# Printrhub_Rev_0_2.net
KiCad netlist of a schematic drawn in EAGLE
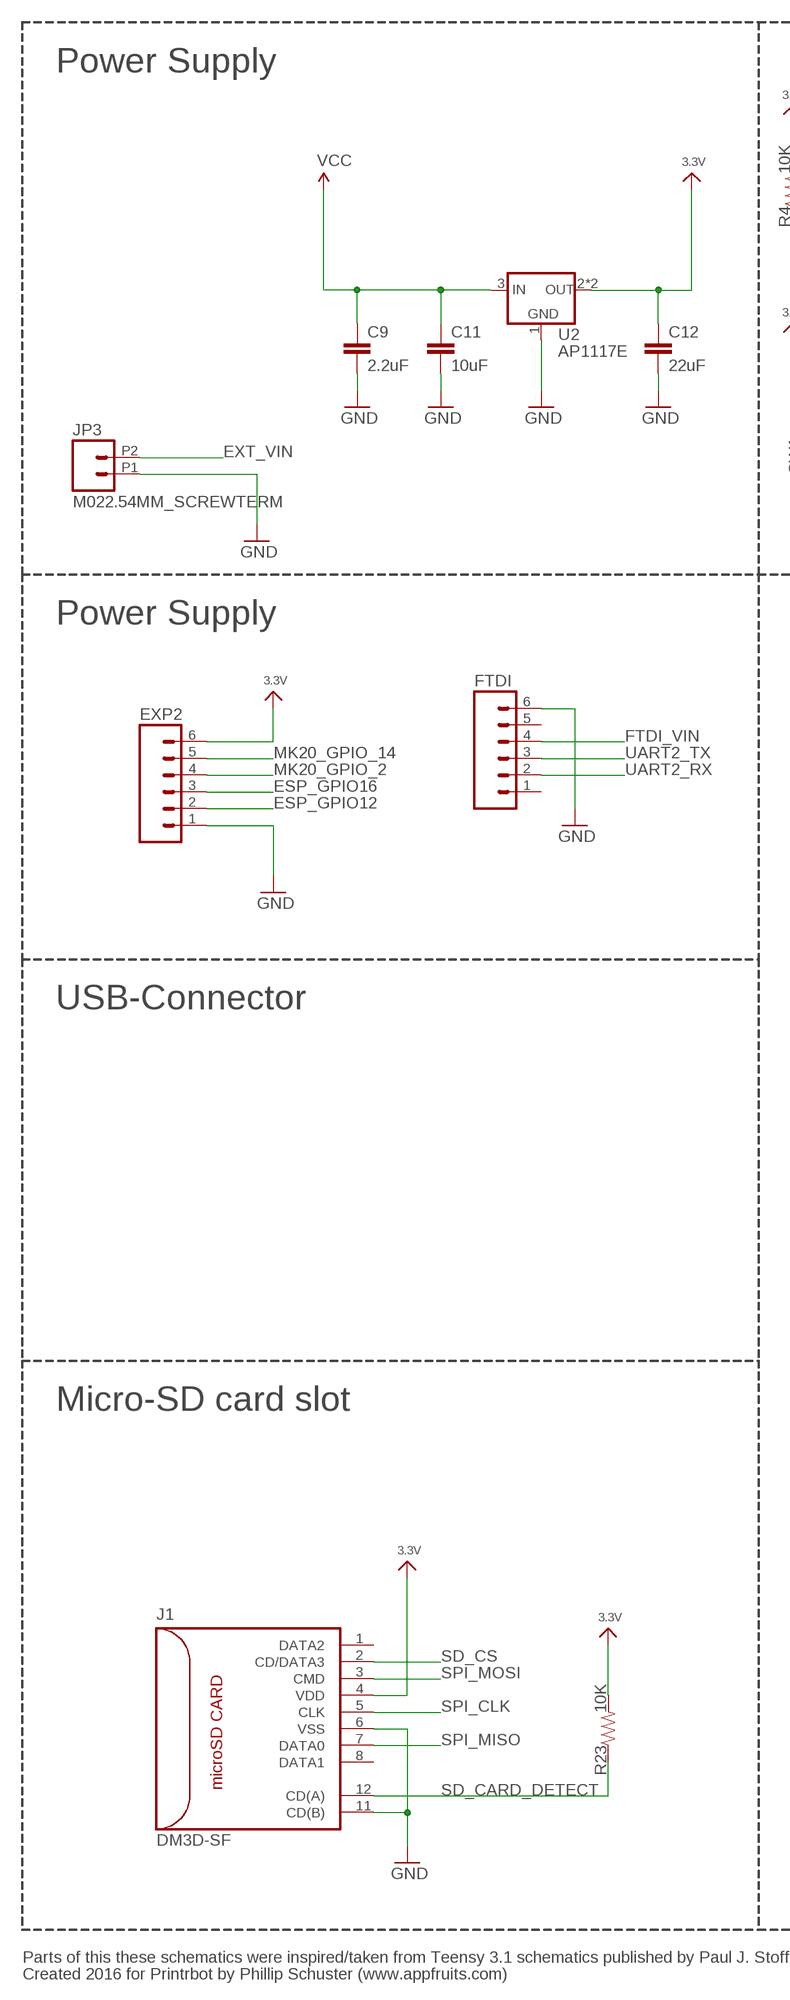
[diagram p0: schematic, sheet 1, part 1 of 2]
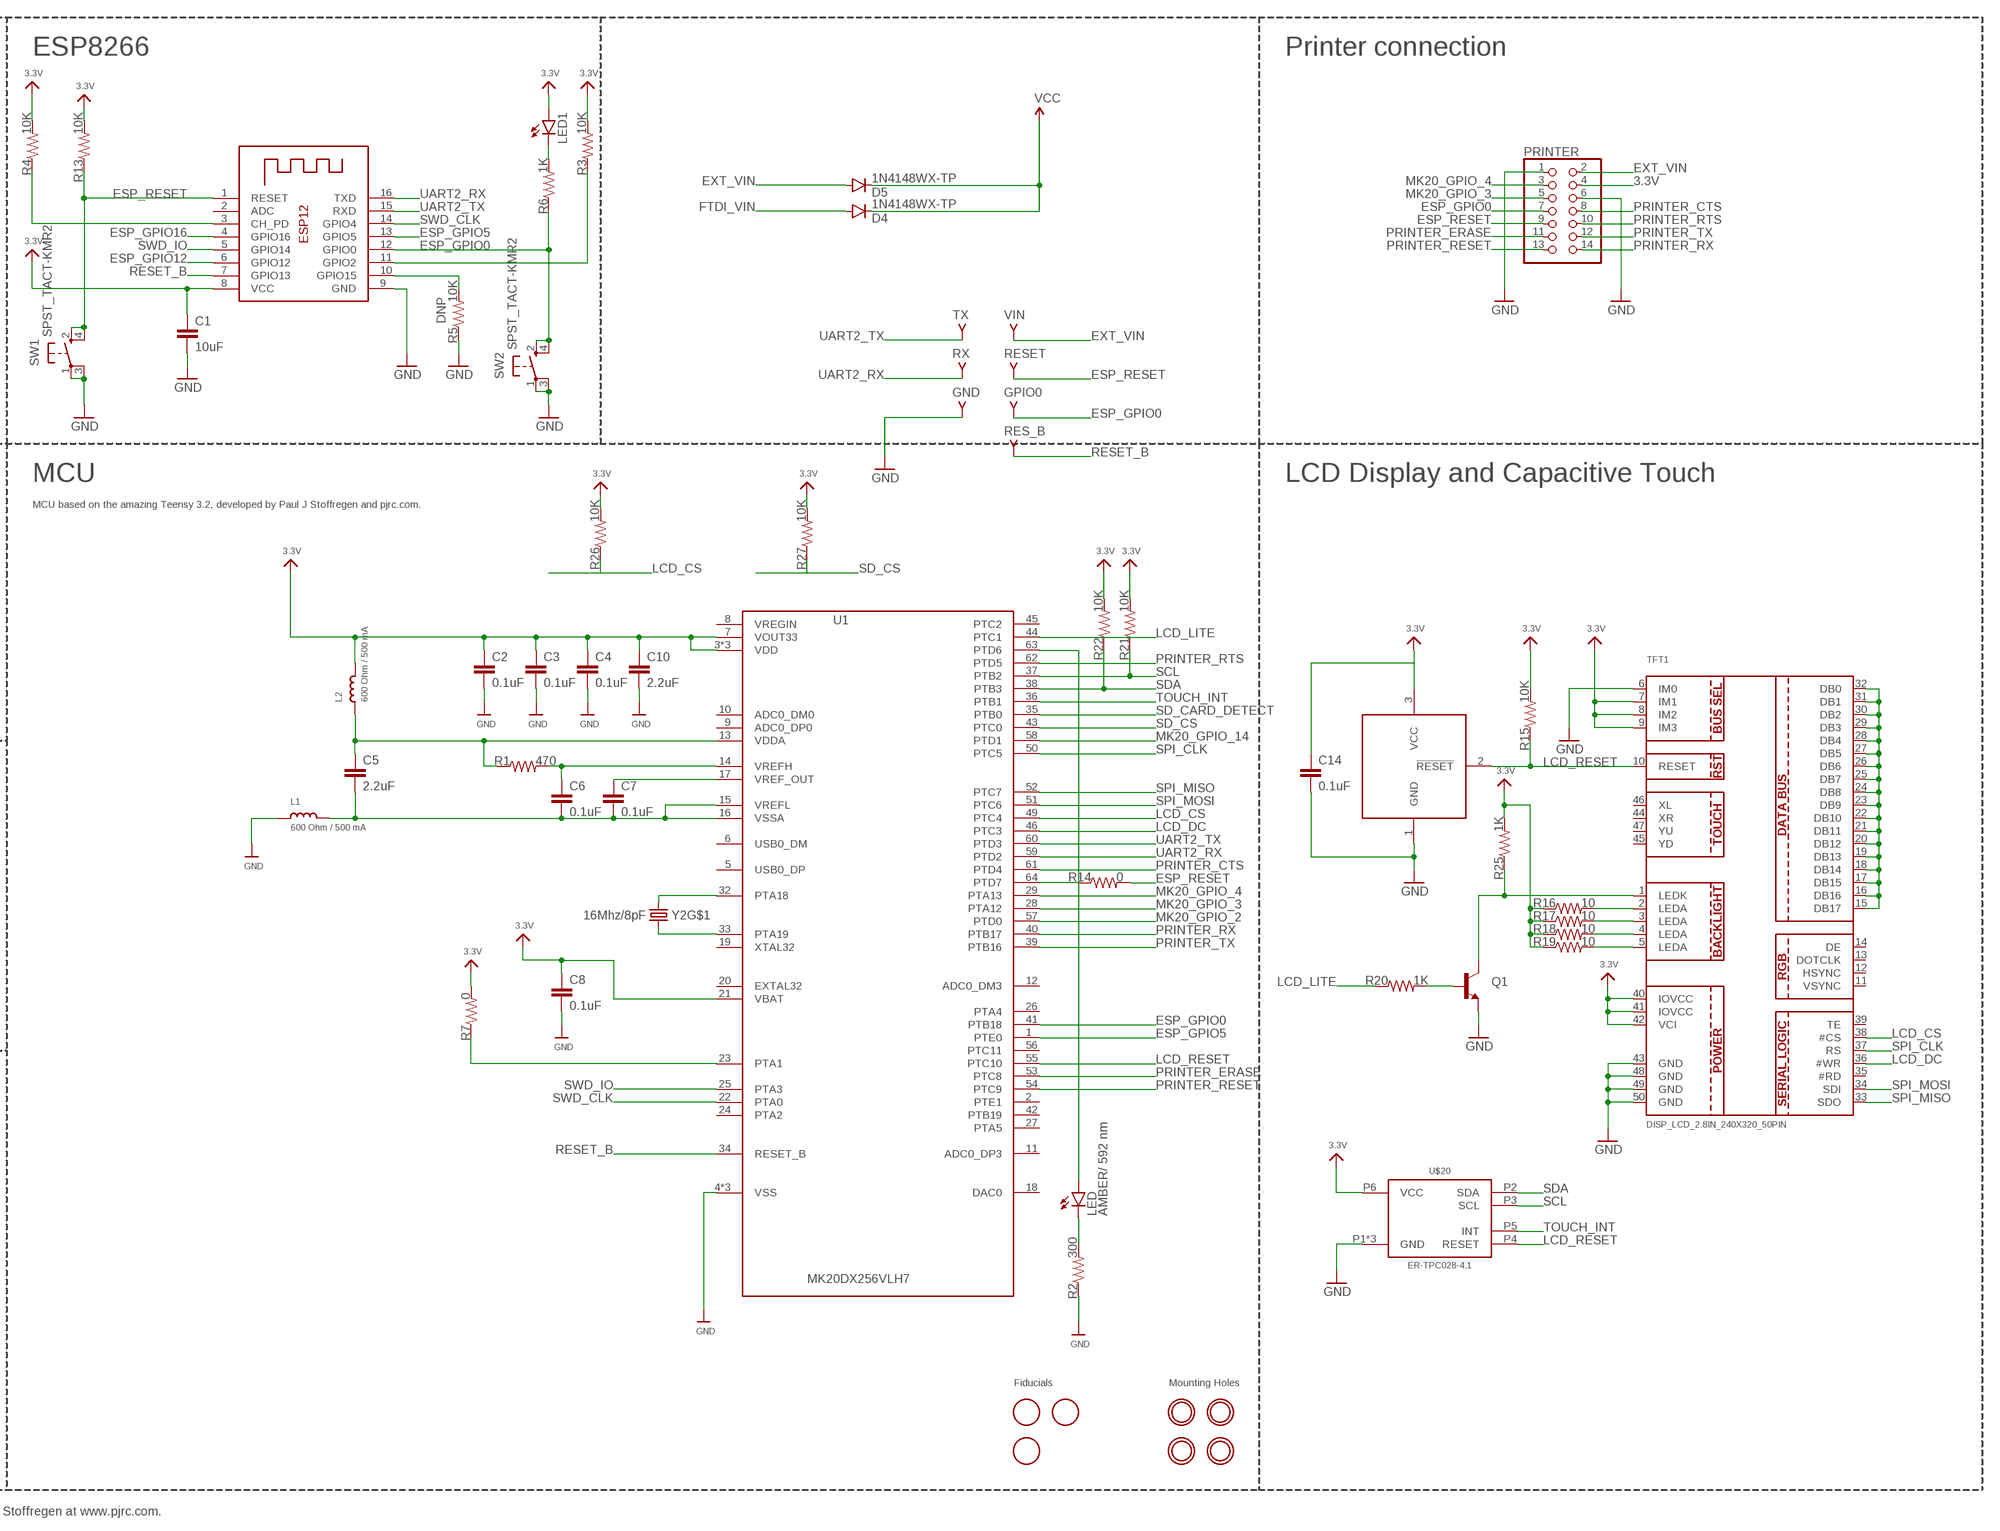
[diagram p1: schematic, sheet 1, part 2 of 2]

(export (version "E")
  (design (tool "Eeschema 10.0.6"))
  (components
    (comp (ref "C1")
      (value "10uF")
      (footprint "eagle-import:0603-CAP")
      (fields (field (name "MF") "Murata") (field (name "MPN") "GRM188R60J106ME47D"))
      (libsource (lib "eagle-import") (part "CAPACITOR-10UF"))
    )
    (comp (ref "C2")
      (value "0.1uF")
      (footprint "eagle-import:0603-CAP")
      (fields (field (name "MF") "Kemet") (field (name "MPN") "C0603C104J3RACTU"))
      (libsource (lib "eagle-import") (part "CAPACITOR-0.1UF"))
    )
    (comp (ref "C3")
      (value "0.1uF")
      (footprint "eagle-import:0603-CAP")
      (fields (field (name "MF") "Kemet") (field (name "MPN") "C0603C104J3RACTU"))
      (libsource (lib "eagle-import") (part "CAPACITOR-0.1UF"))
    )
    (comp (ref "C4")
      (value "0.1uF")
      (footprint "eagle-import:0603-CAP")
      (fields (field (name "MF") "Kemet") (field (name "MPN") "C0603C104J3RACTU"))
      (libsource (lib "eagle-import") (part "CAPACITOR-0.1UF"))
    )
    (comp (ref "C5")
      (value "2.2uF")
      (footprint "eagle-import:0603-CAP")
      (fields (field (name "MF") "Kemet") (field (name "MPN") "C0603C225K4PACTU"))
      (libsource (lib "eagle-import") (part "CAPACITOR-2.2UF"))
    )
    (comp (ref "C6")
      (value "0.1uF")
      (footprint "eagle-import:0603-CAP")
      (fields (field (name "MF") "Kemet") (field (name "MPN") "C0603C104J3RACTU"))
      (libsource (lib "eagle-import") (part "CAPACITOR-0.1UF"))
    )
    (comp (ref "C7")
      (value "0.1uF")
      (footprint "eagle-import:0603-CAP")
      (fields (field (name "MF") "Kemet") (field (name "MPN") "C0603C104J3RACTU"))
      (libsource (lib "eagle-import") (part "CAPACITOR-0.1UF"))
    )
    (comp (ref "C8")
      (value "0.1uF")
      (footprint "eagle-import:0603-CAP")
      (fields (field (name "MF") "Kemet") (field (name "MPN") "C0603C104J3RACTU"))
      (libsource (lib "eagle-import") (part "CAPACITOR-0.1UF"))
    )
    (comp (ref "C9")
      (value "2.2uF")
      (footprint "eagle-import:0603-CAP")
      (fields (field (name "MF") "Kemet") (field (name "MPN") "C0603C225K4PACTU"))
      (libsource (lib "eagle-import") (part "CAPACITOR-2.2UF"))
    )
    (comp (ref "C10")
      (value "2.2uF")
      (footprint "eagle-import:0603-CAP")
      (fields (field (name "MF") "Kemet") (field (name "MPN") "C0603C225K4PACTU"))
      (libsource (lib "eagle-import") (part "CAPACITOR-2.2UF"))
    )
    (comp (ref "C11")
      (value "10uF")
      (footprint "eagle-import:0603-CAP")
      (fields (field (name "MF") "Murata") (field (name "MPN") "GRM188R60J106ME47D"))
      (libsource (lib "eagle-import") (part "CAPACITOR-10UF"))
    )
    (comp (ref "C12")
      (value "22uF")
      (footprint "eagle-import:0603-CAP")
      (fields (field (name "MF") "Murata") (field (name "MPN") "GRM188R60J226MEA0D"))
      (libsource (lib "eagle-import") (part "CAPACITOR-22UF"))
    )
    (comp (ref "C14")
      (value "0.1uF")
      (footprint "eagle-import:0603-CAP")
      (fields (field (name "MF") "Kemet") (field (name "MPN") "C0603C104J3RACTU"))
      (libsource (lib "eagle-import") (part "CAPACITOR-0.1UF"))
    )
    (comp (ref "D4")
      (value "1N4148WX-TP")
      (footprint "eagle-import:SOD-323")
      (fields (field (name "MF") "Micro Commercial Co"))
      (libsource (lib "eagle-import") (part "DIODESOD"))
    )
    (comp (ref "D5")
      (value "1N4148WX-TP")
      (footprint "eagle-import:SOD-323")
      (fields (field (name "MF") "Micro Commercial Co"))
      (libsource (lib "eagle-import") (part "DIODESOD"))
    )
    (comp (ref "EXP2")
      (value "M06SMD-STRAIGHT-ALT")
      (footprint "eagle-import:1X06_SMD_STRAIGHT_ALT")
      (libsource (lib "eagle-import") (part "M06SMD-STRAIGHT-ALT"))
    )
    (comp (ref "FTDI")
      (value "M06SMD-STRAIGHT-ALT")
      (footprint "eagle-import:1X06_SMD_STRAIGHT_ALT")
      (libsource (lib "eagle-import") (part "M06SMD-STRAIGHT-ALT"))
    )
    (comp (ref "GND")
      (value "TPV-SMD-18RN")
      (footprint "eagle-import:SMD-18RN")
      (libsource (lib "eagle-import") (part "TPV-SMD-18RN"))
    )
    (comp (ref "GPIO0")
      (value "TPV-SMD-18RN")
      (footprint "eagle-import:SMD-18RN")
      (libsource (lib "eagle-import") (part "TPV-SMD-18RN"))
    )
    (comp (ref "J1")
      (value "DM3D-SF")
      (footprint "eagle-import:DM3D-SF")
      (libsource (lib "eagle-import") (part "DM3D-SF"))
    )
    (comp (ref "JP3")
      (value "M022.54MM_SCREWTERM")
      (footprint "eagle-import:1X02_2.54_SCREWTERM")
      (libsource (lib "eagle-import") (part "M022.54MM_SCREWTERM"))
    )
    (comp (ref "L1")
      (value "600 Ohm / 500 mA")
      (footprint "eagle-import:0603")
      (fields (field (name "MF") "Murata") (field (name "MPN") "BLM18AG601SN1D"))
      (libsource (lib "eagle-import") (part "INDUCTOR-0603_600OHM/500MA"))
    )
    (comp (ref "L2")
      (value "600 Ohm / 500 mA")
      (footprint "eagle-import:0603")
      (fields (field (name "MF") "Murata") (field (name "MPN") "BLM18AG601SN1D"))
      (libsource (lib "eagle-import") (part "INDUCTOR-0603_600OHM/500MA"))
    )
    (comp (ref "LED")
      (value "AMBER/ 592 nm")
      (footprint "eagle-import:LED-0603")
      (fields (field (name "MF") "Avago Technologies") (field (name "MPN") "HSMA-C190"))
      (libsource (lib "eagle-import") (part "LED-AMBER"))
    )
    (comp (ref "LED1")
      (value "LED-GREEN")
      (footprint "eagle-import:LED-0603")
      (fields (field (name "MF") "Avago") (field (name "MPN") "HSMG-C190"))
      (libsource (lib "eagle-import") (part "LED-GREEN"))
    )
    (comp (ref "PRINTER")
      (value "PINHD-2X7SMT")
      (footprint "eagle-import:2X07_SMT")
      (libsource (lib "eagle-import") (part "PINHD-2X7SMT"))
    )
    (comp (ref "Q1")
      (value "TRANSISTOR_NPNSOT23-3")
      (footprint "eagle-import:SOT23-3")
      (fields (field (name "MF") "ON Semiconductor") (field (name "MPN") "MMBT2222ALT1G"))
      (libsource (lib "eagle-import") (part "TRANSISTOR_NPNSOT23-3"))
    )
    (comp (ref "R1")
      (value "470")
      (footprint "eagle-import:0603-RES")
      (fields (field (name "MF") "Panasonic") (field (name "MPN") "ERJ-3GEYJ471V"))
      (libsource (lib "eagle-import") (part "RESISTOR-470"))
    )
    (comp (ref "R2")
      (value "300")
      (footprint "eagle-import:0603-RES")
      (libsource (lib "eagle-import") (part "RESISTOR0603"))
    )
    (comp (ref "R3")
      (value "10K")
      (footprint "eagle-import:0603-RES")
      (fields (field (name "MF") "Panasonic") (field (name "MPN") "ERJ-3GEYJ103V"))
      (libsource (lib "eagle-import") (part "RESISTOR-10K"))
    )
    (comp (ref "R4")
      (value "10K")
      (footprint "eagle-import:0603-RES")
      (fields (field (name "MF") "Panasonic") (field (name "MPN") "ERJ-3GEYJ103V"))
      (libsource (lib "eagle-import") (part "RESISTOR-10K"))
    )
    (comp (ref "R5")
      (value "10K")
      (footprint "eagle-import:0603-RES")
      (fields (field (name "MF") "Panasonic") (field (name "MPN") "ERJ-3GEYJ103V"))
      (libsource (lib "eagle-import") (part "RESISTOR-10K"))
    )
    (comp (ref "R6")
      (value "1K")
      (footprint "eagle-import:0603-RES")
      (fields (field (name "MF") "Panasonic") (field (name "MPN") "ERJ-3GEYJ102V"))
      (libsource (lib "eagle-import") (part "RESISTOR-1K"))
    )
    (comp (ref "R7")
      (value "0")
      (footprint "eagle-import:0603-RES")
      (fields (field (name "MF") "Panasonic") (field (name "MPN") "ERJ-3GEY0R00V"))
      (libsource (lib "eagle-import") (part "RESISTOR-0"))
    )
    (comp (ref "R13")
      (value "10K")
      (footprint "eagle-import:0603-RES")
      (fields (field (name "MF") "Panasonic") (field (name "MPN") "ERJ-3GEYJ103V"))
      (libsource (lib "eagle-import") (part "RESISTOR-10K"))
    )
    (comp (ref "R14")
      (value "0")
      (footprint "eagle-import:0603-RES")
      (fields (field (name "MF") "Panasonic") (field (name "MPN") "ERJ-3GEY0R00V"))
      (libsource (lib "eagle-import") (part "RESISTOR-0"))
    )
    (comp (ref "R15")
      (value "10K")
      (footprint "eagle-import:0603-RES")
      (fields (field (name "MF") "Panasonic") (field (name "MPN") "ERJ-3GEYJ103V"))
      (libsource (lib "eagle-import") (part "RESISTOR-10K"))
    )
    (comp (ref "R16")
      (value "10")
      (footprint "eagle-import:0603-RES")
      (fields (field (name "MF") "Panasonic") (field (name "MPN") "ERJ-3EKF10R0V"))
      (libsource (lib "eagle-import") (part "RESISTOR-10"))
    )
    (comp (ref "R17")
      (value "10")
      (footprint "eagle-import:0603-RES")
      (fields (field (name "MF") "Panasonic") (field (name "MPN") "ERJ-3EKF10R0V"))
      (libsource (lib "eagle-import") (part "RESISTOR-10"))
    )
    (comp (ref "R18")
      (value "10")
      (footprint "eagle-import:0603-RES")
      (fields (field (name "MF") "Panasonic") (field (name "MPN") "ERJ-3EKF10R0V"))
      (libsource (lib "eagle-import") (part "RESISTOR-10"))
    )
    (comp (ref "R19")
      (value "10")
      (footprint "eagle-import:0603-RES")
      (fields (field (name "MF") "Panasonic") (field (name "MPN") "ERJ-3EKF10R0V"))
      (libsource (lib "eagle-import") (part "RESISTOR-10"))
    )
    (comp (ref "R20")
      (value "1K")
      (footprint "eagle-import:0603-RES")
      (fields (field (name "MF") "Panasonic") (field (name "MPN") "ERJ-3GEYJ102V"))
      (libsource (lib "eagle-import") (part "RESISTOR-1K"))
    )
    (comp (ref "R21")
      (value "10K")
      (footprint "eagle-import:0603-RES")
      (fields (field (name "MF") "Panasonic") (field (name "MPN") "ERJ-3GEYJ103V"))
      (libsource (lib "eagle-import") (part "RESISTOR-10K"))
    )
    (comp (ref "R22")
      (value "10K")
      (footprint "eagle-import:0603-RES")
      (fields (field (name "MF") "Panasonic") (field (name "MPN") "ERJ-3GEYJ103V"))
      (libsource (lib "eagle-import") (part "RESISTOR-10K"))
    )
    (comp (ref "R23")
      (value "10K")
      (footprint "eagle-import:0603-RES")
      (fields (field (name "MF") "Panasonic") (field (name "MPN") "ERJ-3GEYJ103V"))
      (libsource (lib "eagle-import") (part "RESISTOR-10K"))
    )
    (comp (ref "R25")
      (value "1K")
      (footprint "eagle-import:0603-RES")
      (fields (field (name "MF") "Panasonic") (field (name "MPN") "ERJ-3GEYJ102V"))
      (libsource (lib "eagle-import") (part "RESISTOR-1K"))
    )
    (comp (ref "R26")
      (value "10K")
      (footprint "eagle-import:0603-RES")
      (fields (field (name "MF") "Panasonic") (field (name "MPN") "ERJ-3GEYJ103V"))
      (libsource (lib "eagle-import") (part "RESISTOR-10K"))
    )
    (comp (ref "R27")
      (value "10K")
      (footprint "eagle-import:0603-RES")
      (fields (field (name "MF") "Panasonic") (field (name "MPN") "ERJ-3GEYJ103V"))
      (libsource (lib "eagle-import") (part "RESISTOR-10K"))
    )
    (comp (ref "RESET")
      (value "TPV-SMD-18RN")
      (footprint "eagle-import:SMD-18RN")
      (libsource (lib "eagle-import") (part "TPV-SMD-18RN"))
    )
    (comp (ref "RES_B")
      (value "TPV-SMD-18RN")
      (footprint "eagle-import:SMD-18RN")
      (libsource (lib "eagle-import") (part "TPV-SMD-18RN"))
    )
    (comp (ref "RX")
      (value "TPV-SMD-18RN")
      (footprint "eagle-import:SMD-18RN")
      (libsource (lib "eagle-import") (part "TPV-SMD-18RN"))
    )
    (comp (ref "SW1")
      (value "SPST_TACT-KMR2")
      (footprint "eagle-import:KMR2")
      (libsource (lib "eagle-import") (part "SPST_TACT-KMR2"))
    )
    (comp (ref "SW2")
      (value "SPST_TACT-KMR2")
      (footprint "eagle-import:KMR2")
      (libsource (lib "eagle-import") (part "SPST_TACT-KMR2"))
    )
    (comp (ref "TFT1")
      (value "DISP_LCD_2.8IN_240X320_50PIN")
      (footprint "eagle-import:TFT_2.83IN_240X320_50PIN")
      (libsource (lib "eagle-import") (part "DISP_LCD_2.8IN_240X320_50PIN"))
    )
    (comp (ref "TX")
      (value "TPV-SMD-18RN")
      (footprint "eagle-import:SMD-18RN")
      (libsource (lib "eagle-import") (part "TPV-SMD-18RN"))
    )
    (comp (ref "U$15")
      (value "MOUNTINGHOLE2.0")
      (footprint "eagle-import:MOUNTINGHOLE_2.0_PLATED")
      (libsource (lib "eagle-import") (part "MOUNTINGHOLE2.0"))
    )
    (comp (ref "U$16")
      (value "MOUNTINGHOLE2.0")
      (footprint "eagle-import:MOUNTINGHOLE_2.0_PLATED")
      (libsource (lib "eagle-import") (part "MOUNTINGHOLE2.0"))
    )
    (comp (ref "U$17")
      (value "MOUNTINGHOLE2.0")
      (footprint "eagle-import:MOUNTINGHOLE_2.0_PLATED")
      (libsource (lib "eagle-import") (part "MOUNTINGHOLE2.0"))
    )
    (comp (ref "U$18")
      (value "MOUNTINGHOLE2.0")
      (footprint "eagle-import:MOUNTINGHOLE_2.0_PLATED")
      (libsource (lib "eagle-import") (part "MOUNTINGHOLE2.0"))
    )
    (comp (ref "U$20")
      (value "ER-TPC028-4.1")
      (footprint "eagle-import:ER-CON06HB-1")
      (libsource (lib "eagle-import") (part "ER-TPC028-4.1"))
    )
    (comp (ref "U$38")
      (value "FIDUCIAL")
      (footprint "eagle-import:FIDUCIAL_1MM")
      (libsource (lib "eagle-import") (part "FIDUCIAL"))
    )
    (comp (ref "U$39")
      (value "FIDUCIAL")
      (footprint "eagle-import:FIDUCIAL_1MM")
      (libsource (lib "eagle-import") (part "FIDUCIAL"))
    )
    (comp (ref "U$40")
      (value "FIDUCIAL")
      (footprint "eagle-import:FIDUCIAL_1MM")
      (libsource (lib "eagle-import") (part "FIDUCIAL"))
    )
    (comp (ref "U1")
      (value "MK20DX256VLH7")
      (footprint "eagle-import:MK20DX256VLH7")
      (fields (field (name "MF") "Freescale"))
      (libsource (lib "eagle-import") (part "MK20DX256VLH7"))
    )
    (comp (ref "U2")
      (value "AP1117E")
      (footprint "eagle-import:SOT223")
      (libsource (lib "eagle-import") (part "AP1117E"))
    )
    (comp (ref "U3")
      (value "MAX308-SOT23")
      (footprint "eagle-import:SOT23")
      (libsource (lib "eagle-import") (part "MAX308-SOT23"))
    )
    (comp (ref "VIN")
      (value "TPV-SMD-18RN")
      (footprint "eagle-import:SMD-18RN")
      (libsource (lib "eagle-import") (part "TPV-SMD-18RN"))
    )
    (comp (ref "X1")
      (value "ESP-12")
      (footprint "eagle-import:ESP-12")
      (libsource (lib "eagle-import") (part "ESP-12"))
    )
    (comp (ref "Y2")
      (value "16Mhz/8pF")
      (footprint "eagle-import:CRYSTAL-SMD-5X3")
      (fields (field (name "MF") "ECS") (field (name "MPN") "ECS-160-8-30B-CKM"))
      (libsource (lib "eagle-import") (part "CRYSTAL/SMD-5X3-GND16MHZ/8PF"))
    )
  )
  (nets
    (net (code "1") (name "/ESP_GPIO0") (class "Default")
      (node (ref "GPIO0") (pin "TP") (pinfunction "TP_TP") (pintype "passive"))
      (node (ref "PRINTER") (pin "7") (pinfunction "7_7") (pintype "passive"))
      (node (ref "R6") (pin "1") (pinfunction "1_1") (pintype "passive"))
      (node (ref "SW2") (pin "2") (pinfunction "S_2") (pintype "passive"))
      (node (ref "SW2") (pin "4") (pinfunction "S1_4") (pintype "passive"))
      (node (ref "U1") (pin "41") (pinfunction "PTB18_41") (pintype "bidirectional"))
      (node (ref "X1") (pin "12") (pinfunction "GPIO0_12") (pintype "bidirectional"))
    )
    (net (code "2") (name "/ESP_GPIO5") (class "Default")
      (node (ref "U1") (pin "1") (pinfunction "PTE0_1") (pintype "bidirectional"))
      (node (ref "X1") (pin "13") (pinfunction "GPIO5_13") (pintype "bidirectional"))
    )
    (net (code "3") (name "/ESP_GPIO12") (class "Default")
      (node (ref "EXP2") (pin "2") (pinfunction "2_2") (pintype "passive"))
      (node (ref "X1") (pin "6") (pinfunction "GPIO12_6") (pintype "bidirectional"))
    )
    (net (code "4") (name "/ESP_GPIO16") (class "Default")
      (node (ref "EXP2") (pin "3") (pinfunction "3_3") (pintype "passive"))
      (node (ref "X1") (pin "4") (pinfunction "GPIO16_4") (pintype "bidirectional"))
    )
    (net (code "5") (name "/ESP_RESET") (class "Default")
      (node (ref "PRINTER") (pin "9") (pinfunction "9_9") (pintype "passive"))
      (node (ref "R13") (pin "1") (pinfunction "1_1") (pintype "passive"))
      (node (ref "R14") (pin "2") (pinfunction "2_2") (pintype "passive"))
      (node (ref "RESET") (pin "TP") (pinfunction "TP_TP") (pintype "passive"))
      (node (ref "SW1") (pin "2") (pinfunction "S_2") (pintype "passive"))
      (node (ref "SW1") (pin "4") (pinfunction "S1_4") (pintype "passive"))
      (node (ref "X1") (pin "1") (pinfunction "RESET_1") (pintype "input"))
    )
    (net (code "6") (name "/EXT_VIN") (class "Default")
      (node (ref "D5") (pin "A") (pinfunction "A_A") (pintype "passive"))
      (node (ref "JP3") (pin "P2") (pinfunction "2_P2") (pintype "passive"))
      (node (ref "PRINTER") (pin "2") (pinfunction "2_2") (pintype "passive"))
      (node (ref "VIN") (pin "TP") (pinfunction "TP_TP") (pintype "passive"))
    )
    (net (code "7") (name "/FTDI_VIN") (class "Default")
      (node (ref "D4") (pin "A") (pinfunction "A_A") (pintype "passive"))
      (node (ref "FTDI") (pin "4") (pinfunction "4_4") (pintype "passive"))
    )
    (net (code "8") (name "/LCD_CS") (class "Default")
      (node (ref "R26") (pin "1") (pinfunction "1_1") (pintype "passive"))
      (node (ref "TFT1") (pin "38") (pinfunction "#CS_38") (pintype "bidirectional"))
      (node (ref "U1") (pin "49") (pinfunction "PTC4_49") (pintype "bidirectional"))
    )
    (net (code "9") (name "/LCD_DC") (class "Default")
      (node (ref "TFT1") (pin "36") (pinfunction "#WR_36") (pintype "bidirectional"))
      (node (ref "U1") (pin "46") (pinfunction "PTC3_46") (pintype "bidirectional"))
    )
    (net (code "10") (name "/LCD_LITE") (class "Default")
      (node (ref "R20") (pin "1") (pinfunction "1_1") (pintype "passive"))
      (node (ref "U1") (pin "44") (pinfunction "PTC1_44") (pintype "bidirectional"))
    )
    (net (code "11") (name "/LCD_RESET") (class "Default")
      (node (ref "R15") (pin "1") (pinfunction "1_1") (pintype "passive"))
      (node (ref "TFT1") (pin "10") (pinfunction "RESET_10") (pintype "bidirectional"))
      (node (ref "U$20") (pin "P4") (pinfunction "RESET_P4") (pintype "bidirectional"))
      (node (ref "U1") (pin "55") (pinfunction "PTC10_55") (pintype "bidirectional"))
      (node (ref "U3") (pin "2") (pinfunction "~{RESET}_2") (pintype "bidirectional"))
    )
    (net (code "12") (name "/MK20_GPIO_2") (class "Default")
      (node (ref "EXP2") (pin "4") (pinfunction "4_4") (pintype "passive"))
      (node (ref "U1") (pin "57") (pinfunction "PTD0_57") (pintype "bidirectional"))
    )
    (net (code "13") (name "/MK20_GPIO_3") (class "Default")
      (node (ref "PRINTER") (pin "5") (pinfunction "5_5") (pintype "passive"))
      (node (ref "U1") (pin "28") (pinfunction "PTA12_28") (pintype "bidirectional"))
    )
    (net (code "14") (name "/MK20_GPIO_4") (class "Default")
      (node (ref "PRINTER") (pin "3") (pinfunction "3_3") (pintype "passive"))
      (node (ref "U1") (pin "29") (pinfunction "PTA13_29") (pintype "bidirectional"))
    )
    (net (code "15") (name "/MK20_GPIO_14") (class "Default")
      (node (ref "EXP2") (pin "5") (pinfunction "5_5") (pintype "passive"))
      (node (ref "U1") (pin "58") (pinfunction "PTD1_58") (pintype "bidirectional"))
    )
    (net (code "16") (name "/PRINTER_CTS") (class "Default")
      (node (ref "PRINTER") (pin "8") (pinfunction "8_8") (pintype "passive"))
      (node (ref "U1") (pin "61") (pinfunction "PTD4_61") (pintype "bidirectional"))
    )
    (net (code "17") (name "/PRINTER_ERASE") (class "Default")
      (node (ref "PRINTER") (pin "11") (pinfunction "11_11") (pintype "passive"))
      (node (ref "U1") (pin "53") (pinfunction "PTC8_53") (pintype "bidirectional"))
    )
    (net (code "18") (name "/PRINTER_RESET") (class "Default")
      (node (ref "PRINTER") (pin "13") (pinfunction "13_13") (pintype "passive"))
      (node (ref "U1") (pin "54") (pinfunction "PTC9_54") (pintype "bidirectional"))
    )
    (net (code "19") (name "/PRINTER_RTS") (class "Default")
      (node (ref "PRINTER") (pin "10") (pinfunction "10_10") (pintype "passive"))
      (node (ref "U1") (pin "62") (pinfunction "PTD5_62") (pintype "bidirectional"))
    )
    (net (code "20") (name "/PRINTER_RX") (class "Default")
      (node (ref "PRINTER") (pin "14") (pinfunction "14_14") (pintype "passive"))
      (node (ref "U1") (pin "40") (pinfunction "PTB17_40") (pintype "bidirectional"))
    )
    (net (code "21") (name "/PRINTER_TX") (class "Default")
      (node (ref "PRINTER") (pin "12") (pinfunction "12_12") (pintype "passive"))
      (node (ref "U1") (pin "39") (pinfunction "PTB16_39") (pintype "bidirectional"))
    )
    (net (code "22") (name "/RESET_B") (class "Default")
      (node (ref "RES_B") (pin "TP") (pinfunction "TP_TP") (pintype "passive"))
      (node (ref "U1") (pin "34") (pinfunction "RESET_B_34") (pintype "bidirectional"))
      (node (ref "X1") (pin "7") (pinfunction "GPIO13_7") (pintype "bidirectional"))
    )
    (net (code "23") (name "/SCL") (class "Default")
      (node (ref "R21") (pin "1") (pinfunction "1_1") (pintype "passive"))
      (node (ref "U$20") (pin "P3") (pinfunction "SCL_P3") (pintype "bidirectional"))
      (node (ref "U1") (pin "37") (pinfunction "PTB2_37") (pintype "bidirectional"))
    )
    (net (code "24") (name "/SDA") (class "Default")
      (node (ref "R22") (pin "1") (pinfunction "1_1") (pintype "passive"))
      (node (ref "U$20") (pin "P2") (pinfunction "SDA_P2") (pintype "bidirectional"))
      (node (ref "U1") (pin "38") (pinfunction "PTB3_38") (pintype "bidirectional"))
    )
    (net (code "25") (name "/SD_CARD_DETECT") (class "Default")
      (node (ref "J1") (pin "12") (pinfunction "CD(A)_12") (pintype "bidirectional"))
      (node (ref "R23") (pin "1") (pinfunction "1_1") (pintype "passive"))
      (node (ref "U1") (pin "35") (pinfunction "PTB0_35") (pintype "bidirectional"))
    )
    (net (code "26") (name "/SD_CS") (class "Default")
      (node (ref "J1") (pin "2") (pinfunction "CD/DATA3_2") (pintype "bidirectional"))
      (node (ref "R27") (pin "1") (pinfunction "1_1") (pintype "passive"))
      (node (ref "U1") (pin "43") (pinfunction "PTC0_43") (pintype "bidirectional"))
    )
    (net (code "27") (name "/SPI_CLK") (class "Default")
      (node (ref "J1") (pin "5") (pinfunction "CLK_5") (pintype "bidirectional"))
      (node (ref "TFT1") (pin "37") (pinfunction "RS_37") (pintype "bidirectional"))
      (node (ref "U1") (pin "50") (pinfunction "PTC5_50") (pintype "bidirectional"))
    )
    (net (code "28") (name "/SPI_MISO") (class "Default")
      (node (ref "J1") (pin "7") (pinfunction "DATA0_7") (pintype "bidirectional"))
      (node (ref "TFT1") (pin "33") (pinfunction "SDO_33") (pintype "bidirectional"))
      (node (ref "U1") (pin "52") (pinfunction "PTC7_52") (pintype "bidirectional"))
    )
    (net (code "29") (name "/SPI_MOSI") (class "Default")
      (node (ref "J1") (pin "3") (pinfunction "CMD_3") (pintype "bidirectional"))
      (node (ref "TFT1") (pin "34") (pinfunction "SDI_34") (pintype "bidirectional"))
      (node (ref "U1") (pin "51") (pinfunction "PTC6_51") (pintype "bidirectional"))
    )
    (net (code "30") (name "/SWD_CLK") (class "Default")
      (node (ref "U1") (pin "22") (pinfunction "PTA0_22") (pintype "bidirectional"))
      (node (ref "X1") (pin "14") (pinfunction "GPIO4_14") (pintype "bidirectional"))
    )
    (net (code "31") (name "/SWD_IO") (class "Default")
      (node (ref "U1") (pin "25") (pinfunction "PTA3_25") (pintype "bidirectional"))
      (node (ref "X1") (pin "5") (pinfunction "GPIO14_5") (pintype "bidirectional"))
    )
    (net (code "32") (name "/TOUCH_INT") (class "Default")
      (node (ref "U$20") (pin "P5") (pinfunction "INT_P5") (pintype "bidirectional"))
      (node (ref "U1") (pin "36") (pinfunction "PTB1_36") (pintype "bidirectional"))
    )
    (net (code "33") (name "/UART2_RX") (class "Default")
      (node (ref "FTDI") (pin "2") (pinfunction "2_2") (pintype "passive"))
      (node (ref "RX") (pin "TP") (pinfunction "TP_TP") (pintype "passive"))
      (node (ref "U1") (pin "59") (pinfunction "PTD2_59") (pintype "bidirectional"))
      (node (ref "X1") (pin "16") (pinfunction "TXD_16") (pintype "output"))
    )
    (net (code "34") (name "/UART2_TX") (class "Default")
      (node (ref "FTDI") (pin "3") (pinfunction "3_3") (pintype "passive"))
      (node (ref "TX") (pin "TP") (pinfunction "TP_TP") (pintype "passive"))
      (node (ref "U1") (pin "60") (pinfunction "PTD3_60") (pintype "bidirectional"))
      (node (ref "X1") (pin "15") (pinfunction "RXD_15") (pintype "input"))
    )
    (net (code "35") (name "3.3V") (class "Default")
      (node (ref "C1") (pin "1") (pinfunction "1_1") (pintype "passive"))
      (node (ref "C10") (pin "1") (pinfunction "1_1") (pintype "passive"))
      (node (ref "C12") (pin "1") (pinfunction "1_1") (pintype "passive"))
      (node (ref "C14") (pin "1") (pinfunction "1_1") (pintype "passive"))
      (node (ref "C2") (pin "1") (pinfunction "1_1") (pintype "passive"))
      (node (ref "C3") (pin "1") (pinfunction "1_1") (pintype "passive"))
      (node (ref "C4") (pin "1") (pinfunction "1_1") (pintype "passive"))
      (node (ref "C8") (pin "1") (pinfunction "1_1") (pintype "passive"))
      (node (ref "EXP2") (pin "6") (pinfunction "6_6") (pintype "passive"))
      (node (ref "J1") (pin "4") (pinfunction "VDD_4") (pintype "power_in"))
      (node (ref "L2") (pin "2") (pinfunction "2_2") (pintype "passive"))
      (node (ref "LED1") (pin "A") (pinfunction "A_A") (pintype "passive"))
      (node (ref "PRINTER") (pin "4") (pinfunction "4_4") (pintype "passive"))
      (node (ref "R13") (pin "2") (pinfunction "2_2") (pintype "passive"))
      (node (ref "R15") (pin "2") (pinfunction "2_2") (pintype "passive"))
      (node (ref "R16") (pin "1") (pinfunction "1_1") (pintype "passive"))
      (node (ref "R17") (pin "1") (pinfunction "1_1") (pintype "passive"))
      (node (ref "R18") (pin "1") (pinfunction "1_1") (pintype "passive"))
      (node (ref "R19") (pin "1") (pinfunction "1_1") (pintype "passive"))
      (node (ref "R21") (pin "2") (pinfunction "2_2") (pintype "passive"))
      (node (ref "R22") (pin "2") (pinfunction "2_2") (pintype "passive"))
      (node (ref "R23") (pin "2") (pinfunction "2_2") (pintype "passive"))
      (node (ref "R25") (pin "2") (pinfunction "2_2") (pintype "passive"))
      (node (ref "R26") (pin "2") (pinfunction "2_2") (pintype "passive"))
      (node (ref "R27") (pin "2") (pinfunction "2_2") (pintype "passive"))
      (node (ref "R3") (pin "2") (pinfunction "2_2") (pintype "passive"))
      (node (ref "R4") (pin "2") (pinfunction "2_2") (pintype "passive"))
      (node (ref "R7") (pin "2") (pinfunction "2_2") (pintype "passive"))
      (node (ref "TFT1") (pin "40") (pinfunction "IOVCC_40") (pintype "bidirectional"))
      (node (ref "TFT1") (pin "41") (pinfunction "IOVCC_41") (pintype "bidirectional"))
      (node (ref "TFT1") (pin "42") (pinfunction "VCI_42") (pintype "bidirectional"))
      (node (ref "TFT1") (pin "7") (pinfunction "IM1_7") (pintype "bidirectional"))
      (node (ref "TFT1") (pin "8") (pinfunction "IM2_8") (pintype "bidirectional"))
      (node (ref "TFT1") (pin "9") (pinfunction "IM3_9") (pintype "bidirectional"))
      (node (ref "U$20") (pin "P6") (pinfunction "VCC_P6") (pintype "bidirectional"))
      (node (ref "U1") (pin "21") (pinfunction "VBAT_21") (pintype "bidirectional"))
      (node (ref "U1") (pin "3") (pinfunction "VDD_3") (pintype "bidirectional"))
      (node (ref "U1") (pin "30") (pinfunction "VDD_30") (pintype "bidirectional"))
      (node (ref "U1") (pin "48") (pinfunction "VDD_48") (pintype "bidirectional"))
      (node (ref "U1") (pin "7") (pinfunction "VOUT33_7") (pintype "bidirectional"))
      (node (ref "U2") (pin "2") (pinfunction "OUT_2") (pintype "passive"))
      (node (ref "U2") (pin "4") (pinfunction "OUT_4") (pintype "passive"))
      (node (ref "U3") (pin "3") (pinfunction "VCC_3") (pintype "bidirectional"))
      (node (ref "X1") (pin "8") (pinfunction "VCC_8") (pintype "power_in"))
    )
    (net (code "36") (name "GND") (class "Default")
      (node (ref "C1") (pin "2") (pinfunction "2_2") (pintype "passive"))
      (node (ref "C10") (pin "2") (pinfunction "2_2") (pintype "passive"))
      (node (ref "C11") (pin "2") (pinfunction "2_2") (pintype "passive"))
      (node (ref "C12") (pin "2") (pinfunction "2_2") (pintype "passive"))
      (node (ref "C14") (pin "2") (pinfunction "2_2") (pintype "passive"))
      (node (ref "C2") (pin "2") (pinfunction "2_2") (pintype "passive"))
      (node (ref "C3") (pin "2") (pinfunction "2_2") (pintype "passive"))
      (node (ref "C4") (pin "2") (pinfunction "2_2") (pintype "passive"))
      (node (ref "C8") (pin "2") (pinfunction "2_2") (pintype "passive"))
      (node (ref "C9") (pin "2") (pinfunction "2_2") (pintype "passive"))
      (node (ref "EXP2") (pin "1") (pinfunction "1_1") (pintype "passive"))
      (node (ref "FTDI") (pin "6") (pinfunction "6_6") (pintype "passive"))
      (node (ref "GND") (pin "TP") (pinfunction "TP_TP") (pintype "passive"))
      (node (ref "J1") (pin "11") (pinfunction "CD(B)_11") (pintype "bidirectional"))
      (node (ref "J1") (pin "6") (pinfunction "VSS_6") (pintype "power_in"))
      (node (ref "JP3") (pin "P1") (pinfunction "1_P1") (pintype "passive"))
      (node (ref "L1") (pin "1") (pinfunction "1_1") (pintype "passive"))
      (node (ref "PRINTER") (pin "1") (pinfunction "1_1") (pintype "passive"))
      (node (ref "PRINTER") (pin "6") (pinfunction "6_6") (pintype "passive"))
      (node (ref "Q1") (pin "2") (pinfunction "E_2") (pintype "passive"))
      (node (ref "R2") (pin "1") (pinfunction "1_1") (pintype "passive"))
      (node (ref "R5") (pin "1") (pinfunction "1_1") (pintype "passive"))
      (node (ref "SW1") (pin "1") (pinfunction "P_1") (pintype "passive"))
      (node (ref "SW1") (pin "3") (pinfunction "P1_3") (pintype "passive"))
      (node (ref "SW2") (pin "1") (pinfunction "P_1") (pintype "passive"))
      (node (ref "SW2") (pin "3") (pinfunction "P1_3") (pintype "passive"))
      (node (ref "TFT1") (pin "43") (pinfunction "GND_43") (pintype "bidirectional"))
      (node (ref "TFT1") (pin "48") (pinfunction "GND_48") (pintype "bidirectional"))
      (node (ref "TFT1") (pin "49") (pinfunction "GND_49") (pintype "bidirectional"))
      (node (ref "TFT1") (pin "50") (pinfunction "GND_50") (pintype "bidirectional"))
      (node (ref "TFT1") (pin "6") (pinfunction "IM0_6") (pintype "bidirectional"))
      (node (ref "U$20") (pin "P1") (pinfunction "GND_P1") (pintype "bidirectional"))
      (node (ref "U$20") (pin "PAD@0") (pinfunction "GND_PAD@0") (pintype "bidirectional"))
      (node (ref "U$20") (pin "PAD@1") (pinfunction "GND_PAD@1") (pintype "bidirectional"))
      (node (ref "U1") (pin "31") (pinfunction "VSS_31") (pintype "bidirectional"))
      (node (ref "U1") (pin "4") (pinfunction "VSS_4") (pintype "bidirectional"))
      (node (ref "U1") (pin "47") (pinfunction "VSS_47") (pintype "bidirectional"))
      (node (ref "U2") (pin "1") (pinfunction "GND_1") (pintype "input"))
      (node (ref "U3") (pin "1") (pinfunction "GND_1") (pintype "bidirectional"))
      (node (ref "X1") (pin "9") (pinfunction "GND_9") (pintype "power_in"))
    )
    (net (code "37") (name "Net-(LED-PadC)") (class "Default")
      (node (ref "LED") (pin "C") (pinfunction "C_C") (pintype "passive"))
      (node (ref "R2") (pin "2") (pinfunction "2_2") (pintype "passive"))
    )
    (net (code "38") (name "Net-(LED1-PadC)") (class "Default")
      (node (ref "LED1") (pin "C") (pinfunction "C_C") (pintype "passive"))
      (node (ref "R6") (pin "2") (pinfunction "2_2") (pintype "passive"))
    )
    (net (code "39") (name "Net-(Q1-B)") (class "Default")
      (node (ref "Q1") (pin "1") (pinfunction "B_1") (pintype "passive"))
      (node (ref "R20") (pin "2") (pinfunction "2_2") (pintype "passive"))
    )
    (net (code "40") (name "Net-(Q1-C)") (class "Default")
      (node (ref "Q1") (pin "3") (pinfunction "C_3") (pintype "passive"))
      (node (ref "R25") (pin "1") (pinfunction "1_1") (pintype "passive"))
      (node (ref "TFT1") (pin "1") (pinfunction "LEDK_1") (pintype "bidirectional"))
    )
    (net (code "41") (name "Net-(R16-Pad2)") (class "Default")
      (node (ref "R16") (pin "2") (pinfunction "2_2") (pintype "passive"))
      (node (ref "TFT1") (pin "2") (pinfunction "LEDA_2") (pintype "bidirectional"))
    )
    (net (code "42") (name "Net-(R17-Pad2)") (class "Default")
      (node (ref "R17") (pin "2") (pinfunction "2_2") (pintype "passive"))
      (node (ref "TFT1") (pin "3") (pinfunction "LEDA_3") (pintype "bidirectional"))
    )
    (net (code "43") (name "Net-(R18-Pad2)") (class "Default")
      (node (ref "R18") (pin "2") (pinfunction "2_2") (pintype "passive"))
      (node (ref "TFT1") (pin "4") (pinfunction "LEDA_4") (pintype "bidirectional"))
    )
    (net (code "44") (name "Net-(R19-Pad2)") (class "Default")
      (node (ref "R19") (pin "2") (pinfunction "2_2") (pintype "passive"))
      (node (ref "TFT1") (pin "5") (pinfunction "LEDA_5") (pintype "bidirectional"))
    )
    (net (code "45") (name "Net-(TFT1-DB0)") (class "Default")
      (node (ref "TFT1") (pin "15") (pinfunction "DB17_15") (pintype "bidirectional"))
      (node (ref "TFT1") (pin "16") (pinfunction "DB16_16") (pintype "bidirectional"))
      (node (ref "TFT1") (pin "17") (pinfunction "DB15_17") (pintype "bidirectional"))
      (node (ref "TFT1") (pin "18") (pinfunction "DB14_18") (pintype "bidirectional"))
      (node (ref "TFT1") (pin "19") (pinfunction "DB13_19") (pintype "bidirectional"))
      (node (ref "TFT1") (pin "20") (pinfunction "DB12_20") (pintype "bidirectional"))
      (node (ref "TFT1") (pin "21") (pinfunction "DB11_21") (pintype "bidirectional"))
      (node (ref "TFT1") (pin "22") (pinfunction "DB10_22") (pintype "bidirectional"))
      (node (ref "TFT1") (pin "23") (pinfunction "DB9_23") (pintype "bidirectional"))
      (node (ref "TFT1") (pin "24") (pinfunction "DB8_24") (pintype "bidirectional"))
      (node (ref "TFT1") (pin "25") (pinfunction "DB7_25") (pintype "bidirectional"))
      (node (ref "TFT1") (pin "26") (pinfunction "DB6_26") (pintype "bidirectional"))
      (node (ref "TFT1") (pin "27") (pinfunction "DB5_27") (pintype "bidirectional"))
      (node (ref "TFT1") (pin "28") (pinfunction "DB4_28") (pintype "bidirectional"))
      (node (ref "TFT1") (pin "29") (pinfunction "DB3_29") (pintype "bidirectional"))
      (node (ref "TFT1") (pin "30") (pinfunction "DB2_30") (pintype "bidirectional"))
      (node (ref "TFT1") (pin "31") (pinfunction "DB1_31") (pintype "bidirectional"))
      (node (ref "TFT1") (pin "32") (pinfunction "DB0_32") (pintype "bidirectional"))
    )
    (net (code "46") (name "Net-(U1-PTA1)") (class "Default")
      (node (ref "R7") (pin "1") (pinfunction "1_1") (pintype "passive"))
      (node (ref "U1") (pin "23") (pinfunction "PTA1_23") (pintype "bidirectional"))
    )
    (net (code "47") (name "Net-(U1-PTA18)") (class "Default")
      (node (ref "U1") (pin "32") (pinfunction "PTA18_32") (pintype "bidirectional"))
      (node (ref "Y2") (pin "3") (pinfunction "2_3") (pintype "passive"))
    )
    (net (code "48") (name "Net-(U1-PTA19)") (class "Default")
      (node (ref "U1") (pin "33") (pinfunction "PTA19_33") (pintype "bidirectional"))
      (node (ref "Y2") (pin "1") (pinfunction "1_1") (pintype "passive"))
    )
    (net (code "49") (name "Net-(U1-PTD6)") (class "Default")
      (node (ref "LED") (pin "A") (pinfunction "A_A") (pintype "passive"))
      (node (ref "U1") (pin "63") (pinfunction "PTD6_63") (pintype "bidirectional"))
    )
    (net (code "50") (name "Net-(U1-PTD7)") (class "Default")
      (node (ref "R14") (pin "1") (pinfunction "1_1") (pintype "passive"))
      (node (ref "U1") (pin "64") (pinfunction "PTD7_64") (pintype "bidirectional"))
    )
    (net (code "51") (name "Net-(U1-VDDA)") (class "Default")
      (node (ref "C5") (pin "1") (pinfunction "1_1") (pintype "passive"))
      (node (ref "L2") (pin "1") (pinfunction "1_1") (pintype "passive"))
      (node (ref "R1") (pin "1") (pinfunction "1_1") (pintype "passive"))
      (node (ref "U1") (pin "13") (pinfunction "VDDA_13") (pintype "bidirectional"))
    )
    (net (code "52") (name "Net-(U1-VREFH)") (class "Default")
      (node (ref "C6") (pin "1") (pinfunction "1_1") (pintype "passive"))
      (node (ref "R1") (pin "2") (pinfunction "2_2") (pintype "passive"))
      (node (ref "U1") (pin "14") (pinfunction "VREFH_14") (pintype "bidirectional"))
    )
    (net (code "53") (name "Net-(U1-VREFL)") (class "Default")
      (node (ref "C5") (pin "2") (pinfunction "2_2") (pintype "passive"))
      (node (ref "C6") (pin "2") (pinfunction "2_2") (pintype "passive"))
      (node (ref "C7") (pin "2") (pinfunction "2_2") (pintype "passive"))
      (node (ref "L1") (pin "2") (pinfunction "2_2") (pintype "passive"))
      (node (ref "U1") (pin "15") (pinfunction "VREFL_15") (pintype "bidirectional"))
      (node (ref "U1") (pin "16") (pinfunction "VSSA_16") (pintype "bidirectional"))
    )
    (net (code "54") (name "Net-(U1-VREF_OUT)") (class "Default")
      (node (ref "C7") (pin "1") (pinfunction "1_1") (pintype "passive"))
      (node (ref "U1") (pin "17") (pinfunction "VREF_OUT_17") (pintype "bidirectional"))
    )
    (net (code "55") (name "Net-(X1-CH_PD)") (class "Default")
      (node (ref "R4") (pin "1") (pinfunction "1_1") (pintype "passive"))
      (node (ref "X1") (pin "3") (pinfunction "CH_PD_3") (pintype "input"))
    )
    (net (code "56") (name "Net-(X1-GPIO2)") (class "Default")
      (node (ref "R3") (pin "1") (pinfunction "1_1") (pintype "passive"))
      (node (ref "X1") (pin "11") (pinfunction "GPIO2_11") (pintype "bidirectional"))
    )
    (net (code "57") (name "Net-(X1-GPIO15)") (class "Default")
      (node (ref "R5") (pin "2") (pinfunction "2_2") (pintype "passive"))
      (node (ref "X1") (pin "10") (pinfunction "GPIO15_10") (pintype "bidirectional"))
    )
    (net (code "58") (name "VCC") (class "Default")
      (node (ref "C11") (pin "1") (pinfunction "1_1") (pintype "passive"))
      (node (ref "C9") (pin "1") (pinfunction "1_1") (pintype "passive"))
      (node (ref "D4") (pin "C") (pinfunction "C_C") (pintype "passive"))
      (node (ref "D5") (pin "C") (pinfunction "C_C") (pintype "passive"))
      (node (ref "U2") (pin "3") (pinfunction "IN_3") (pintype "input"))
    )
    (net (code "59") (name "unconnected-(FTDI-Pad1)") (class "Default")
      (node (ref "FTDI") (pin "1") (pinfunction "1_1") (pintype "passive"))
    )
    (net (code "60") (name "unconnected-(FTDI-Pad5)") (class "Default")
      (node (ref "FTDI") (pin "5") (pinfunction "5_5") (pintype "passive"))
    )
    (net (code "61") (name "unconnected-(J1B-DATA1-Pad8)") (class "Default")
      (node (ref "J1") (pin "8") (pinfunction "DATA1_8") (pintype "bidirectional"))
    )
    (net (code "62") (name "unconnected-(J1B-DATA2-Pad1)") (class "Default")
      (node (ref "J1") (pin "1") (pinfunction "DATA2_1") (pintype "bidirectional"))
    )
    (net (code "63") (name "unconnected-(TFT1-#RD-Pad35)") (class "Default")
      (node (ref "TFT1") (pin "35") (pinfunction "#RD_35") (pintype "bidirectional"))
    )
    (net (code "64") (name "unconnected-(TFT1-DE-Pad14)") (class "Default")
      (node (ref "TFT1") (pin "14") (pinfunction "DE_14") (pintype "bidirectional"))
    )
    (net (code "65") (name "unconnected-(TFT1-DOTCLK-Pad13)") (class "Default")
      (node (ref "TFT1") (pin "13") (pinfunction "DOTCLK_13") (pintype "bidirectional"))
    )
    (net (code "66") (name "unconnected-(TFT1-HSYNC-Pad12)") (class "Default")
      (node (ref "TFT1") (pin "12") (pinfunction "HSYNC_12") (pintype "bidirectional"))
    )
    (net (code "67") (name "unconnected-(TFT1-TE-Pad39)") (class "Default")
      (node (ref "TFT1") (pin "39") (pinfunction "TE_39") (pintype "bidirectional"))
    )
    (net (code "68") (name "unconnected-(TFT1-VSYNC-Pad11)") (class "Default")
      (node (ref "TFT1") (pin "11") (pinfunction "VSYNC_11") (pintype "bidirectional"))
    )
    (net (code "69") (name "unconnected-(TFT1-XL-Pad46)") (class "Default")
      (node (ref "TFT1") (pin "46") (pinfunction "XL_46") (pintype "bidirectional"))
    )
    (net (code "70") (name "unconnected-(TFT1-XR-Pad44)") (class "Default")
      (node (ref "TFT1") (pin "44") (pinfunction "XR_44") (pintype "bidirectional"))
    )
    (net (code "71") (name "unconnected-(TFT1-YD-Pad45)") (class "Default")
      (node (ref "TFT1") (pin "45") (pinfunction "YD_45") (pintype "bidirectional"))
    )
    (net (code "72") (name "unconnected-(TFT1-YU-Pad47)") (class "Default")
      (node (ref "TFT1") (pin "47") (pinfunction "YU_47") (pintype "bidirectional"))
    )
    (net (code "73") (name "unconnected-(U1-ADC0_DM0-Pad10)") (class "Default")
      (node (ref "U1") (pin "10") (pinfunction "ADC0_DM0_10") (pintype "bidirectional"))
    )
    (net (code "74") (name "unconnected-(U1-ADC0_DM3-Pad12)") (class "Default")
      (node (ref "U1") (pin "12") (pinfunction "ADC0_DM3_12") (pintype "bidirectional"))
    )
    (net (code "75") (name "unconnected-(U1-ADC0_DP0-Pad9)") (class "Default")
      (node (ref "U1") (pin "9") (pinfunction "ADC0_DP0_9") (pintype "bidirectional"))
    )
    (net (code "76") (name "unconnected-(U1-ADC0_DP3-Pad11)") (class "Default")
      (node (ref "U1") (pin "11") (pinfunction "ADC0_DP3_11") (pintype "bidirectional"))
    )
    (net (code "77") (name "unconnected-(U1-DAC0-Pad18)") (class "Default")
      (node (ref "U1") (pin "18") (pinfunction "DAC0_18") (pintype "bidirectional"))
    )
    (net (code "78") (name "unconnected-(U1-EXTAL32-Pad20)") (class "Default")
      (node (ref "U1") (pin "20") (pinfunction "EXTAL32_20") (pintype "bidirectional"))
    )
    (net (code "79") (name "unconnected-(U1-PTA2-Pad24)") (class "Default")
      (node (ref "U1") (pin "24") (pinfunction "PTA2_24") (pintype "bidirectional"))
    )
    (net (code "80") (name "unconnected-(U1-PTA4-Pad26)") (class "Default")
      (node (ref "U1") (pin "26") (pinfunction "PTA4_26") (pintype "bidirectional"))
    )
    (net (code "81") (name "unconnected-(U1-PTA5-Pad27)") (class "Default")
      (node (ref "U1") (pin "27") (pinfunction "PTA5_27") (pintype "bidirectional"))
    )
    (net (code "82") (name "unconnected-(U1-PTB19-Pad42)") (class "Default")
      (node (ref "U1") (pin "42") (pinfunction "PTB19_42") (pintype "bidirectional"))
    )
    (net (code "83") (name "unconnected-(U1-PTC2-Pad45)") (class "Default")
      (node (ref "U1") (pin "45") (pinfunction "PTC2_45") (pintype "bidirectional"))
    )
    (net (code "84") (name "unconnected-(U1-PTC11-Pad56)") (class "Default")
      (node (ref "U1") (pin "56") (pinfunction "PTC11_56") (pintype "bidirectional"))
    )
    (net (code "85") (name "unconnected-(U1-PTE1-Pad2)") (class "Default")
      (node (ref "U1") (pin "2") (pinfunction "PTE1_2") (pintype "bidirectional"))
    )
    (net (code "86") (name "unconnected-(U1-USB0_DM-Pad6)") (class "Default")
      (node (ref "U1") (pin "6") (pinfunction "USB0_DM_6") (pintype "bidirectional"))
    )
    (net (code "87") (name "unconnected-(U1-USB0_DP-Pad5)") (class "Default")
      (node (ref "U1") (pin "5") (pinfunction "USB0_DP_5") (pintype "bidirectional"))
    )
    (net (code "88") (name "unconnected-(U1-VREGIN-Pad8)") (class "Default")
      (node (ref "U1") (pin "8") (pinfunction "VREGIN_8") (pintype "bidirectional"))
    )
    (net (code "89") (name "unconnected-(U1-XTAL32-Pad19)") (class "Default")
      (node (ref "U1") (pin "19") (pinfunction "XTAL32_19") (pintype "bidirectional"))
    )
    (net (code "90") (name "unconnected-(X1-ADC-Pad2)") (class "Default")
      (node (ref "X1") (pin "2") (pinfunction "ADC_2") (pintype "passive"))
    )
  )
)
